# Adapter_DIP_AVR.net
KiCad netlist of a schematic drawn in Altium Designer
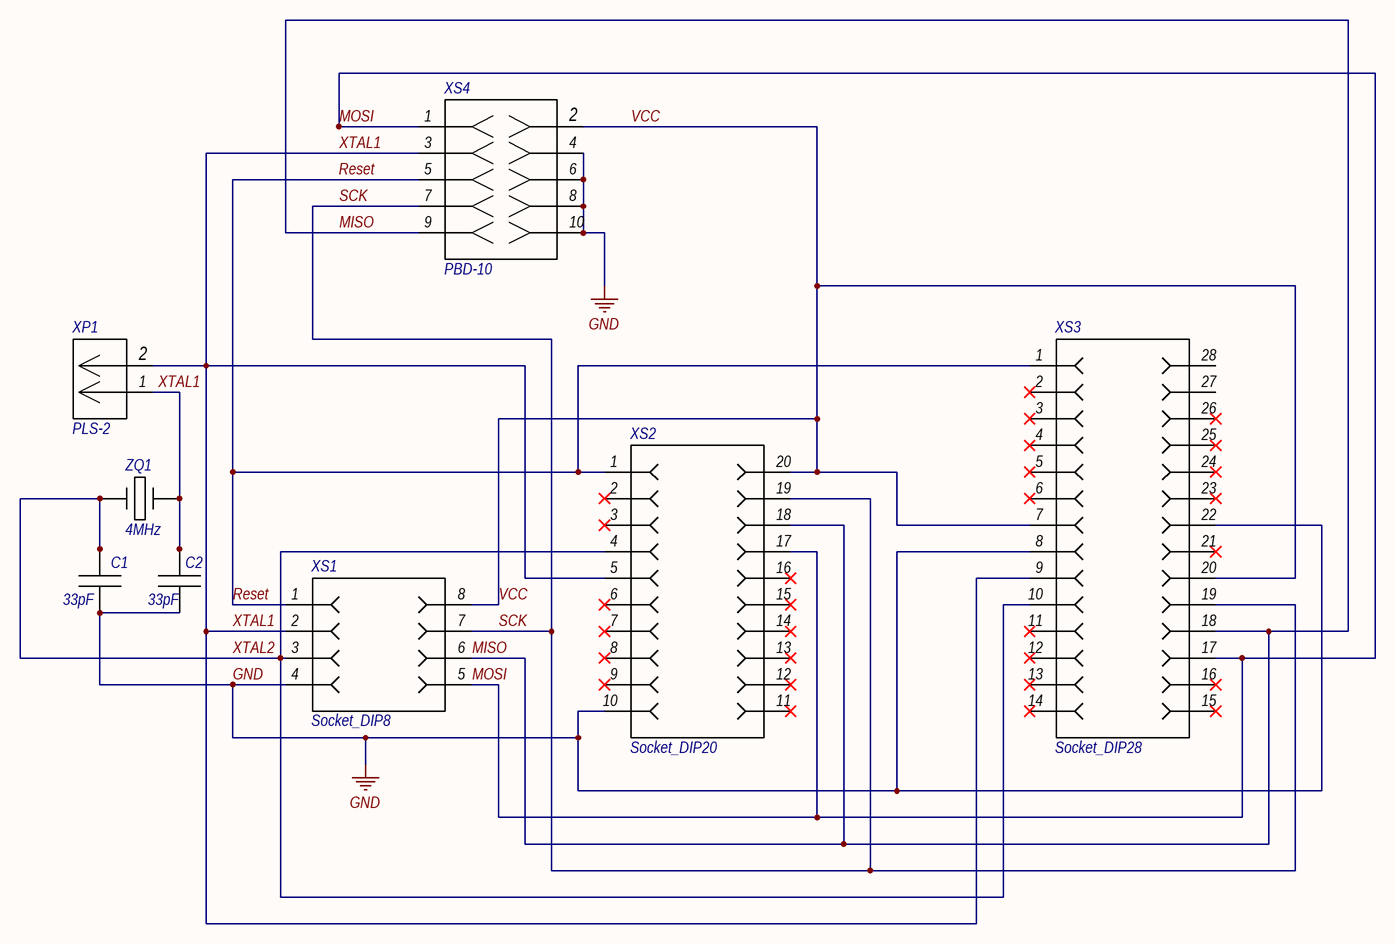
[diagram p0: Adapter_DIP_AVR.SchDoc]

(export (version "E")
  (design (tool "Eeschema 10.0.6"))
  (components
    (comp (ref "C1") (value "33pF") (footprint "Capasitors") (libsource (lib "Schlib1") (part "CAP")))
    (comp (ref "C2") (value "33pF") (footprint "Capasitors") (libsource (lib "Schlib1") (part "CAP")))
    (comp (ref "XP1") (value "PLS-2") (footprint "PLS-2") (libsource (lib "Schlib1") (part "PLS-2")))
    (comp (ref "XS1")
      (value "Socket_DIP8")
      (footprint "Socket_DIP8")
      (libsource (lib "Schlib1") (part "Socket_DIP8"))
    )
    (comp (ref "XS2")
      (value "Socket_DIP20")
      (footprint "Socket_DIP20")
      (libsource (lib "Schlib1") (part "Socket_DIP20"))
    )
    (comp (ref "XS3")
      (value "Socket_DIP28")
      (footprint "Socket_DIP28")
      (libsource (lib "Schlib1") (part "Socket_DIP28"))
    )
    (comp (ref "XS4") (value "PBD-10") (footprint "PBD-10") (libsource (lib "Schlib1") (part "PBD-10")))
    (comp (ref "ZQ1") (value "4MHz") (footprint "HC-49S") (libsource (lib "Schlib1") (part "Crystal")))
  )
  (nets
    (net (code "1") (name "/MISO") (class "Default")
      (node (ref "XS1") (pin "6") (pinfunction "6_6") (pintype "passive"))
      (node (ref "XS2") (pin "18") (pinfunction "18_18") (pintype "passive"))
      (node (ref "XS3") (pin "18") (pinfunction "18_18") (pintype "passive"))
      (node (ref "XS4") (pin "9") (pinfunction "9_9") (pintype "passive"))
    )
    (net (code "2") (name "/MOSI") (class "Default")
      (node (ref "XS1") (pin "5") (pinfunction "5_5") (pintype "passive"))
      (node (ref "XS2") (pin "17") (pinfunction "17_17") (pintype "passive"))
      (node (ref "XS3") (pin "17") (pinfunction "17_17") (pintype "passive"))
      (node (ref "XS4") (pin "1") (pintype "passive"))
    )
    (net (code "3") (name "/Reset") (class "Default")
      (node (ref "XS1") (pin "1") (pinfunction "1_1") (pintype "passive"))
      (node (ref "XS2") (pin "1") (pinfunction "1_1") (pintype "passive"))
      (node (ref "XS3") (pin "1") (pinfunction "1_1") (pintype "passive"))
      (node (ref "XS4") (pin "5") (pinfunction "5_5") (pintype "passive"))
    )
    (net (code "4") (name "/SCK") (class "Default")
      (node (ref "XS1") (pin "7") (pinfunction "7_7") (pintype "passive"))
      (node (ref "XS2") (pin "19") (pinfunction "19_19") (pintype "passive"))
      (node (ref "XS3") (pin "19") (pinfunction "19_19") (pintype "passive"))
      (node (ref "XS4") (pin "7") (pinfunction "7_7") (pintype "passive"))
    )
    (net (code "5") (name "/VCC") (class "Default")
      (node (ref "XS1") (pin "8") (pinfunction "8_8") (pintype "passive"))
      (node (ref "XS2") (pin "20") (pinfunction "20_20") (pintype "passive"))
      (node (ref "XS3") (pin "20") (pinfunction "20_20") (pintype "passive"))
      (node (ref "XS3") (pin "7") (pinfunction "7_7") (pintype "passive"))
      (node (ref "XS4") (pin "2") (pintype "passive"))
    )
    (net (code "6") (name "/XTAL1") (class "Default")
      (node (ref "C2") (pin "2") (pinfunction "2_2") (pintype "passive"))
      (node (ref "XP1") (pin "1") (pintype "passive"))
      (node (ref "XP1") (pin "2") (pintype "passive"))
      (node (ref "XS1") (pin "2") (pinfunction "2_2") (pintype "passive"))
      (node (ref "XS2") (pin "5") (pinfunction "5_5") (pintype "passive"))
      (node (ref "XS3") (pin "9") (pinfunction "9_9") (pintype "passive"))
      (node (ref "XS4") (pin "3") (pinfunction "3_3") (pintype "passive"))
      (node (ref "ZQ1") (pin "2") (pinfunction "14_2") (pintype "passive"))
    )
    (net (code "7") (name "/XTAL2") (class "Default")
      (node (ref "C1") (pin "2") (pinfunction "2_2") (pintype "passive"))
      (node (ref "XS1") (pin "3") (pinfunction "3_3") (pintype "passive"))
      (node (ref "XS2") (pin "4") (pinfunction "4_4") (pintype "passive"))
      (node (ref "XS3") (pin "10") (pinfunction "10_10") (pintype "passive"))
      (node (ref "ZQ1") (pin "1") (pinfunction "13_1") (pintype "passive"))
    )
    (net (code "8") (name "GND") (class "Default")
      (node (ref "C1") (pin "1") (pinfunction "1_1") (pintype "passive"))
      (node (ref "C2") (pin "1") (pinfunction "1_1") (pintype "passive"))
      (node (ref "XS1") (pin "4") (pinfunction "4_4") (pintype "passive"))
      (node (ref "XS2") (pin "10") (pinfunction "10_10") (pintype "passive"))
      (node (ref "XS3") (pin "22") (pinfunction "22_22") (pintype "passive"))
      (node (ref "XS3") (pin "8") (pinfunction "8_8") (pintype "passive"))
      (node (ref "XS4") (pin "10") (pinfunction "10_10") (pintype "passive"))
      (node (ref "XS4") (pin "4") (pinfunction "4_4") (pintype "passive"))
      (node (ref "XS4") (pin "6") (pinfunction "6_6") (pintype "passive"))
      (node (ref "XS4") (pin "8") (pinfunction "8_8") (pintype "passive"))
    )
    (net (code "9") (name "unconnected-(XS2-Pad2)") (class "Default")
      (node (ref "XS2") (pin "2") (pinfunction "2_2") (pintype "passive+no_connect"))
    )
    (net (code "10") (name "unconnected-(XS2-Pad3)") (class "Default")
      (node (ref "XS2") (pin "3") (pinfunction "3_3") (pintype "passive+no_connect"))
    )
    (net (code "11") (name "unconnected-(XS2-Pad6)") (class "Default")
      (node (ref "XS2") (pin "6") (pinfunction "6_6") (pintype "passive+no_connect"))
    )
    (net (code "12") (name "unconnected-(XS2-Pad7)") (class "Default")
      (node (ref "XS2") (pin "7") (pinfunction "7_7") (pintype "passive+no_connect"))
    )
    (net (code "13") (name "unconnected-(XS2-Pad8)") (class "Default")
      (node (ref "XS2") (pin "8") (pinfunction "8_8") (pintype "passive+no_connect"))
    )
    (net (code "14") (name "unconnected-(XS2-Pad9)") (class "Default")
      (node (ref "XS2") (pin "9") (pinfunction "9_9") (pintype "passive+no_connect"))
    )
    (net (code "15") (name "unconnected-(XS2-Pad11)") (class "Default")
      (node (ref "XS2") (pin "11") (pinfunction "11_11") (pintype "passive+no_connect"))
    )
    (net (code "16") (name "unconnected-(XS2-Pad12)") (class "Default")
      (node (ref "XS2") (pin "12") (pinfunction "12_12") (pintype "passive+no_connect"))
    )
    (net (code "17") (name "unconnected-(XS2-Pad13)") (class "Default")
      (node (ref "XS2") (pin "13") (pinfunction "13_13") (pintype "passive+no_connect"))
    )
    (net (code "18") (name "unconnected-(XS2-Pad14)") (class "Default")
      (node (ref "XS2") (pin "14") (pinfunction "14_14") (pintype "passive+no_connect"))
    )
    (net (code "19") (name "unconnected-(XS2-Pad15)") (class "Default")
      (node (ref "XS2") (pin "15") (pinfunction "15_15") (pintype "passive+no_connect"))
    )
    (net (code "20") (name "unconnected-(XS2-Pad16)") (class "Default")
      (node (ref "XS2") (pin "16") (pinfunction "16_16") (pintype "passive+no_connect"))
    )
    (net (code "21") (name "unconnected-(XS3-Pad2)") (class "Default")
      (node (ref "XS3") (pin "2") (pinfunction "2_2") (pintype "passive+no_connect"))
    )
    (net (code "22") (name "unconnected-(XS3-Pad3)") (class "Default")
      (node (ref "XS3") (pin "3") (pinfunction "3_3") (pintype "passive+no_connect"))
    )
    (net (code "23") (name "unconnected-(XS3-Pad4)") (class "Default")
      (node (ref "XS3") (pin "4") (pinfunction "4_4") (pintype "passive+no_connect"))
    )
    (net (code "24") (name "unconnected-(XS3-Pad5)") (class "Default")
      (node (ref "XS3") (pin "5") (pinfunction "5_5") (pintype "passive+no_connect"))
    )
    (net (code "25") (name "unconnected-(XS3-Pad6)") (class "Default")
      (node (ref "XS3") (pin "6") (pinfunction "6_6") (pintype "passive+no_connect"))
    )
    (net (code "26") (name "unconnected-(XS3-Pad11)") (class "Default")
      (node (ref "XS3") (pin "11") (pinfunction "11_11") (pintype "passive+no_connect"))
    )
    (net (code "27") (name "unconnected-(XS3-Pad12)") (class "Default")
      (node (ref "XS3") (pin "12") (pinfunction "12_12") (pintype "passive+no_connect"))
    )
    (net (code "28") (name "unconnected-(XS3-Pad13)") (class "Default")
      (node (ref "XS3") (pin "13") (pinfunction "13_13") (pintype "passive+no_connect"))
    )
    (net (code "29") (name "unconnected-(XS3-Pad14)") (class "Default")
      (node (ref "XS3") (pin "14") (pinfunction "14_14") (pintype "passive+no_connect"))
    )
    (net (code "30") (name "unconnected-(XS3-Pad15)") (class "Default")
      (node (ref "XS3") (pin "15") (pinfunction "15_15") (pintype "passive+no_connect"))
    )
    (net (code "31") (name "unconnected-(XS3-Pad16)") (class "Default")
      (node (ref "XS3") (pin "16") (pinfunction "16_16") (pintype "passive+no_connect"))
    )
    (net (code "32") (name "unconnected-(XS3-Pad21)") (class "Default")
      (node (ref "XS3") (pin "21") (pinfunction "21_21") (pintype "passive+no_connect"))
    )
    (net (code "33") (name "unconnected-(XS3-Pad23)") (class "Default")
      (node (ref "XS3") (pin "23") (pinfunction "23_23") (pintype "passive+no_connect"))
    )
    (net (code "34") (name "unconnected-(XS3-Pad24)") (class "Default")
      (node (ref "XS3") (pin "24") (pinfunction "24_24") (pintype "passive+no_connect"))
    )
    (net (code "35") (name "unconnected-(XS3-Pad25)") (class "Default")
      (node (ref "XS3") (pin "25") (pinfunction "25_25") (pintype "passive+no_connect"))
    )
    (net (code "36") (name "unconnected-(XS3-Pad26)") (class "Default")
      (node (ref "XS3") (pin "26") (pinfunction "26_26") (pintype "passive+no_connect"))
    )
    (net (code "37") (name "unconnected-(XS3-Pad27)") (class "Default")
      (node (ref "XS3") (pin "27") (pinfunction "27_27") (pintype "passive"))
    )
    (net (code "38") (name "unconnected-(XS3-Pad28)") (class "Default")
      (node (ref "XS3") (pin "28") (pinfunction "28_28") (pintype "passive"))
    )
  )
)
